# source_eagle.net
KiCad netlist of a schematic drawn in EAGLE
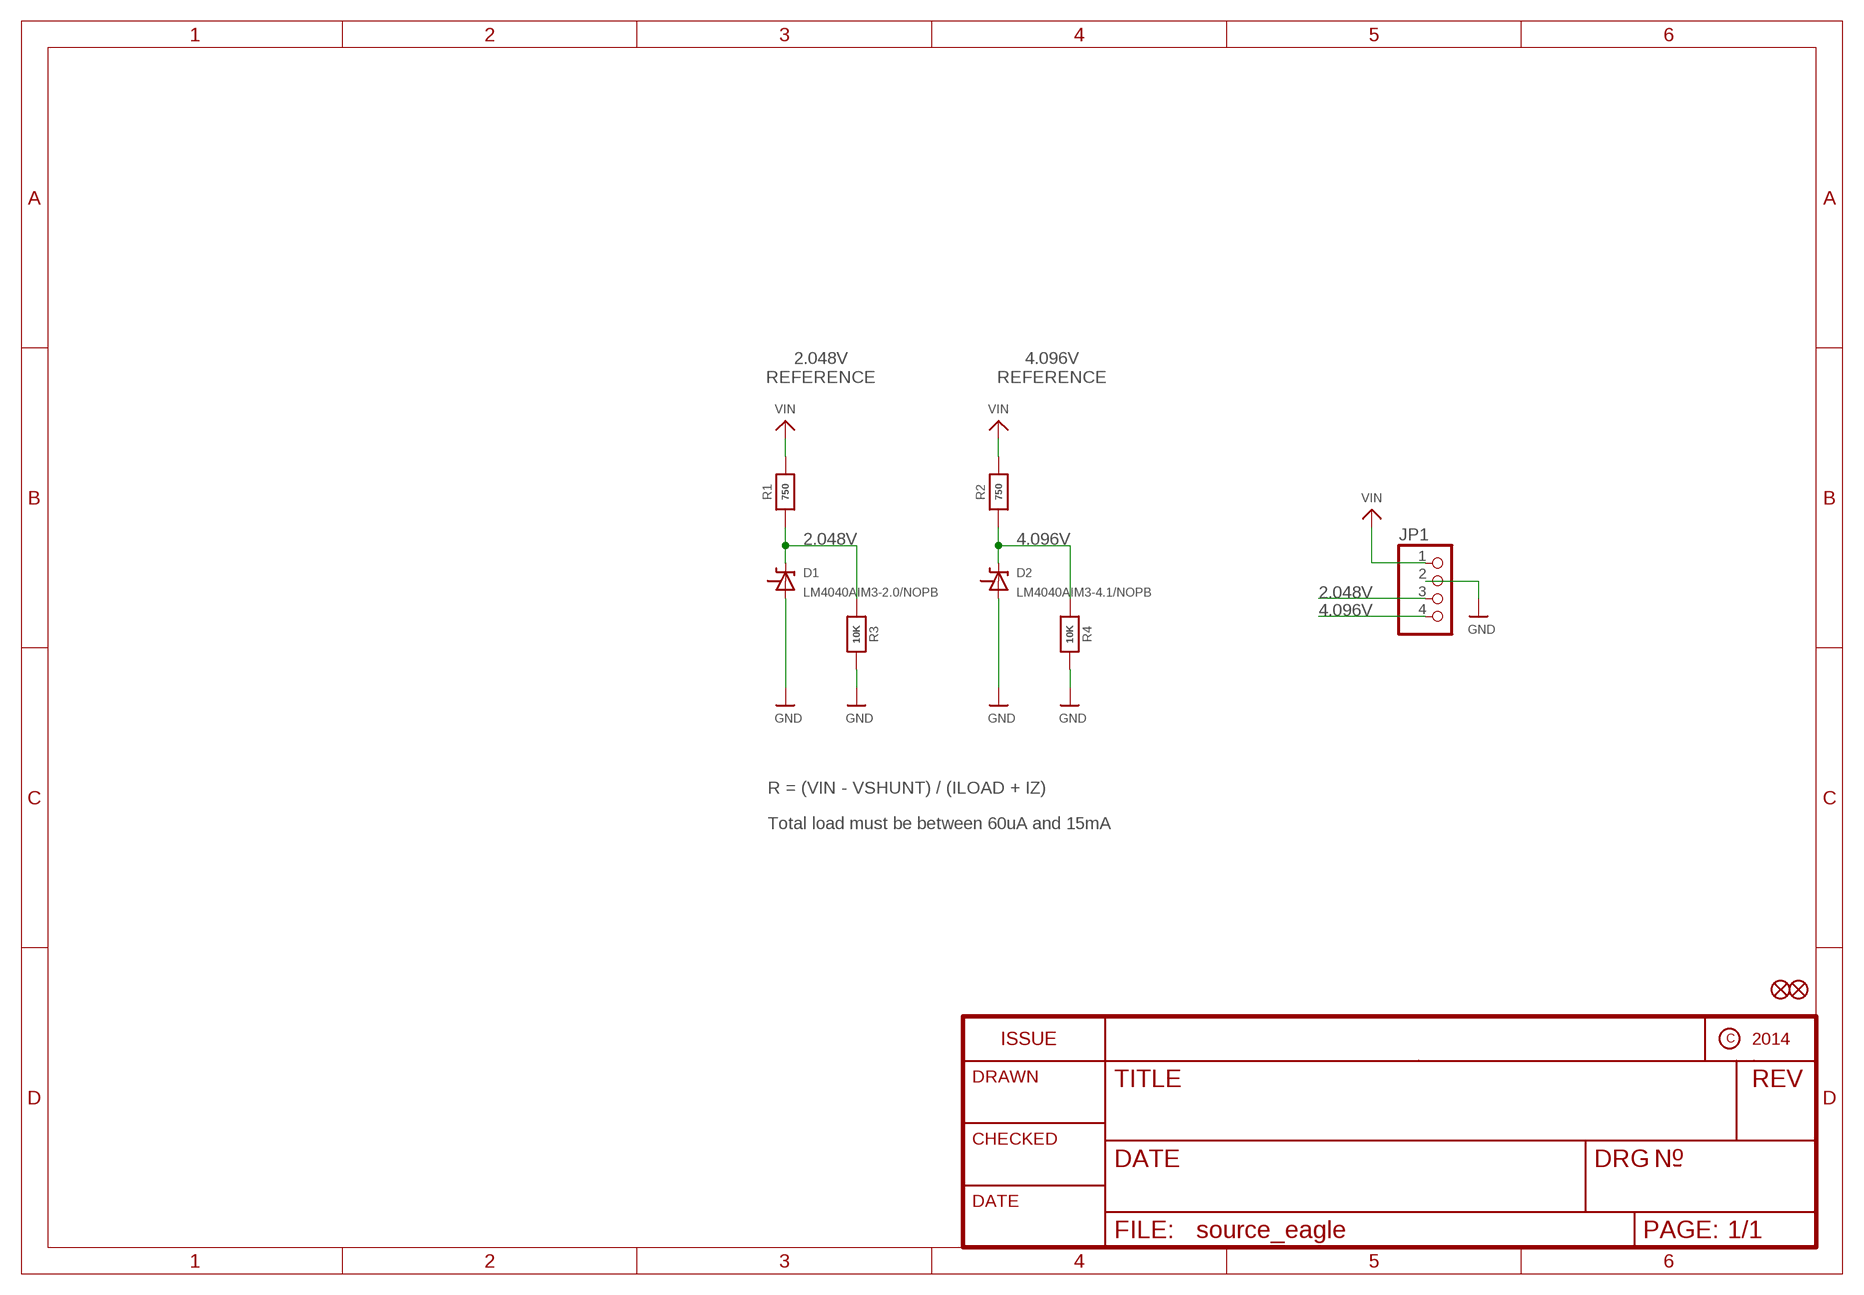
[diagram p0: schematic, sheet 1]

(export (version "E")
  (design (tool "Eeschema 10.0.6"))
  (components
    (comp (ref "D1")
      (value "LM4040AIM3-2.0/NOPB")
      (footprint "eagle-import:SOT23-R")
      (libsource (lib "eagle-import") (part "VREF_SHUNT"))
    )
    (comp (ref "D2")
      (value "LM4040AIM3-4.1/NOPB")
      (footprint "eagle-import:SOT23-R")
      (libsource (lib "eagle-import") (part "VREF_SHUNT"))
    )
    (comp (ref "FID1")
      (value "FIDUCIAL\"\"")
      (footprint "eagle-import:FIDUCIAL_1MM")
      (libsource (lib "eagle-import") (part "FIDUCIAL{dblquote}{dblquote}"))
    )
    (comp (ref "FID2")
      (value "FIDUCIAL\"\"")
      (footprint "eagle-import:FIDUCIAL_1MM")
      (libsource (lib "eagle-import") (part "FIDUCIAL{dblquote}{dblquote}"))
    )
    (comp (ref "JP1")
      (value "HEADER-1X4ROUND")
      (footprint "eagle-import:1X04_ROUND")
      (libsource (lib "eagle-import") (part "HEADER-1X4ROUND"))
    )
    (comp (ref "R1")
      (value "750")
      (footprint "eagle-import:0805-NO")
      (libsource (lib "eagle-import") (part "RESISTOR0805_NOOUTLINE"))
    )
    (comp (ref "R2")
      (value "750")
      (footprint "eagle-import:0805-NO")
      (libsource (lib "eagle-import") (part "RESISTOR0805_NOOUTLINE"))
    )
    (comp (ref "R3")
      (value "10K")
      (footprint "eagle-import:0805-NO")
      (libsource (lib "eagle-import") (part "RESISTOR0805_NOOUTLINE"))
    )
    (comp (ref "R4")
      (value "10K")
      (footprint "eagle-import:0805-NO")
      (libsource (lib "eagle-import") (part "RESISTOR0805_NOOUTLINE"))
    )
  )
  (nets
    (net (code "1") (name "/2.048V") (class "Default")
      (node (ref "D1") (pin "1") (pinfunction "+_1") (pintype "passive"))
      (node (ref "JP1") (pin "3") (pinfunction "3_3") (pintype "passive"))
      (node (ref "R1") (pin "1") (pinfunction "1_1") (pintype "passive"))
      (node (ref "R3") (pin "1") (pinfunction "1_1") (pintype "passive"))
    )
    (net (code "2") (name "/4.096V") (class "Default")
      (node (ref "D2") (pin "1") (pinfunction "+_1") (pintype "passive"))
      (node (ref "JP1") (pin "4") (pinfunction "4_4") (pintype "passive"))
      (node (ref "R2") (pin "1") (pinfunction "1_1") (pintype "passive"))
      (node (ref "R4") (pin "1") (pinfunction "1_1") (pintype "passive"))
    )
    (net (code "3") (name "GND") (class "Default")
      (node (ref "D1") (pin "2") (pinfunction "-_2") (pintype "passive"))
      (node (ref "D2") (pin "2") (pinfunction "-_2") (pintype "passive"))
      (node (ref "JP1") (pin "2") (pinfunction "2_2") (pintype "passive"))
      (node (ref "R3") (pin "2") (pinfunction "2_2") (pintype "passive"))
      (node (ref "R4") (pin "2") (pinfunction "2_2") (pintype "passive"))
    )
    (net (code "4") (name "VIN") (class "Default")
      (node (ref "JP1") (pin "1") (pinfunction "1_1") (pintype "passive"))
      (node (ref "R1") (pin "2") (pinfunction "2_2") (pintype "passive"))
      (node (ref "R2") (pin "2") (pinfunction "2_2") (pintype "passive"))
    )
    (net (code "5") (name "unconnected-(D1-NC-Pad3)") (class "Default")
      (node (ref "D1") (pin "3") (pinfunction "NC_3") (pintype "passive"))
    )
    (net (code "6") (name "unconnected-(D2-NC-Pad3)") (class "Default")
      (node (ref "D2") (pin "3") (pinfunction "NC_3") (pintype "passive"))
    )
  )
)
